# RatDBS-NoBattery.net
KiCad netlist of a schematic drawn in EAGLE
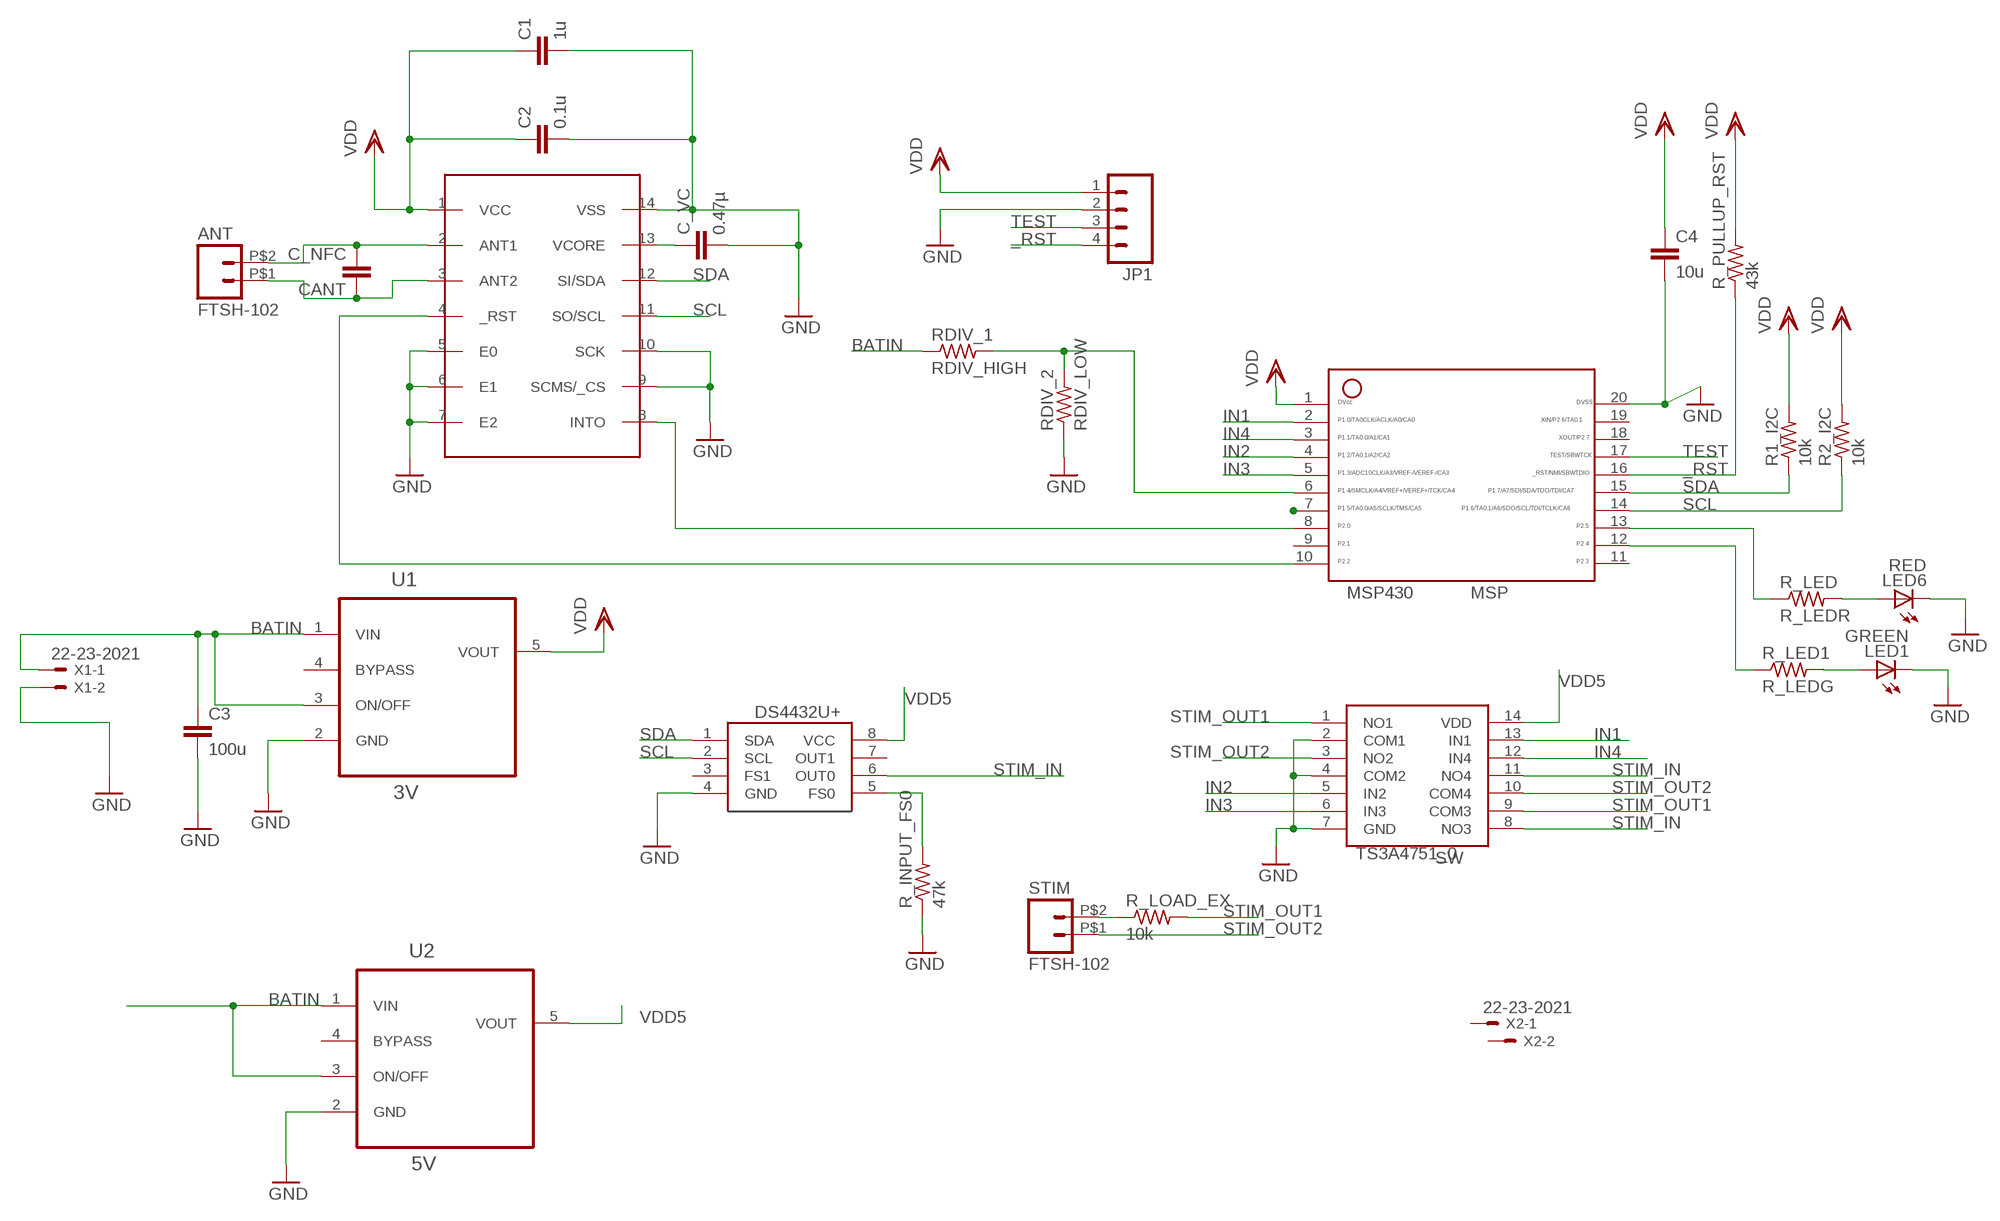
[diagram p0: schematic, sheet 1]

(export (version "E")
  (design (tool "Eeschema 10.0.6"))
  (components
    (comp (ref "ANT")
      (value "FTSH-102")
      (footprint "eagle-import:FTSH-102-DH")
      (libsource (lib "eagle-import") (part "FTSH-102"))
    )
    (comp (ref "C1")
      (value "1u")
      (footprint "eagle-import:C0603")
      (libsource (lib "eagle-import") (part "C-EUC0603"))
    )
    (comp (ref "C2")
      (value "0.1u")
      (footprint "eagle-import:C0603")
      (libsource (lib "eagle-import") (part "C-EUC0603"))
    )
    (comp (ref "C3")
      (value "100u")
      (footprint "eagle-import:C1206")
      (libsource (lib "eagle-import") (part "C-EUC1206"))
    )
    (comp (ref "C4")
      (value "10u")
      (footprint "eagle-import:C1206")
      (libsource (lib "eagle-import") (part "C-EUC1206"))
    )
    (comp (ref "CANT")
      (value "C_NFC")
      (footprint "eagle-import:C0603")
      (libsource (lib "eagle-import") (part "C-EUC0603"))
    )
    (comp (ref "C_VC")
      (value "0.47µ")
      (footprint "eagle-import:C0603")
      (libsource (lib "eagle-import") (part "C-EUC0603"))
    )
    (comp (ref "DS4432U+")
      (value "DS4432U+")
      (footprint "eagle-import:8_PIN")
      (libsource (lib "eagle-import") (part "DS4432U+"))
    )
    (comp (ref "JP1")
      (value "M041.27MM")
      (footprint "eagle-import:1X04-1.27MM")
      (libsource (lib "eagle-import") (part "M041.27MM"))
    )
    (comp (ref "LED1")
      (value "GREEN")
      (footprint "eagle-import:LED-1206")
      (libsource (lib "eagle-import") (part "LED1206"))
    )
    (comp (ref "LED6")
      (value "RED")
      (footprint "eagle-import:LED-1206")
      (libsource (lib "eagle-import") (part "LED1206"))
    )
    (comp (ref "MSP430")
      (value "MSP")
      (footprint "eagle-import:20_PIN")
      (libsource (lib "eagle-import") (part "MSP430"))
    )
    (comp (ref "R1_I2C")
      (value "10k")
      (footprint "eagle-import:R0603")
      (libsource (lib "eagle-import") (part "R-US_R0603"))
    )
    (comp (ref "R2_I2C")
      (value "10k")
      (footprint "eagle-import:R0603")
      (libsource (lib "eagle-import") (part "R-US_R0603"))
    )
    (comp (ref "RDIV_1")
      (value "RDIV_HIGH")
      (footprint "eagle-import:R0603")
      (libsource (lib "eagle-import") (part "R-US_R0603"))
    )
    (comp (ref "RDIV_2")
      (value "RDIV_LOW")
      (footprint "eagle-import:R0603")
      (libsource (lib "eagle-import") (part "R-US_R0603"))
    )
    (comp (ref "R_INPUT_FS0")
      (value "47k")
      (footprint "eagle-import:R0603")
      (libsource (lib "eagle-import") (part "R-US_R0603"))
    )
    (comp (ref "R_LED")
      (value "R_LEDR")
      (footprint "eagle-import:R0603")
      (libsource (lib "eagle-import") (part "R-US_R0603"))
    )
    (comp (ref "R_LED1")
      (value "R_LEDG")
      (footprint "eagle-import:R0603")
      (libsource (lib "eagle-import") (part "R-US_R0603"))
    )
    (comp (ref "R_LOAD_EX")
      (value "10k")
      (footprint "eagle-import:R0603")
      (libsource (lib "eagle-import") (part "R-US_R0603"))
    )
    (comp (ref "R_PULLUP_RST")
      (value "43k")
      (footprint "eagle-import:R0603")
      (libsource (lib "eagle-import") (part "R-US_R0603"))
    )
    (comp (ref "STIM")
      (value "FTSH-102")
      (footprint "eagle-import:FTSH-102-DH")
      (libsource (lib "eagle-import") (part "FTSH-102"))
    )
    (comp (ref "TS3A4751_0")
      (value "SW")
      (footprint "eagle-import:14_PIN")
      (libsource (lib "eagle-import") (part "TS3A4751"))
    )
    (comp (ref "U$1")
      (value "NFC")
      (footprint "eagle-import:PW_R-PDSO-G14")
      (libsource (lib "eagle-import") (part "RF430CL330H"))
    )
    (comp (ref "U1")
      (value "3V")
      (footprint "eagle-import:SOT95P280X145-5N")
      (fields (field (name "MPN") "LP2985A-33DBVTE4"))
      (libsource (lib "eagle-import") (part "LP2985A-33DBVTE4"))
    )
    (comp (ref "U2")
      (value "5V")
      (footprint "eagle-import:SOT95P280X145-5N")
      (fields (field (name "MPN") "LP2985A-33DBVTE4"))
      (libsource (lib "eagle-import") (part "LP2985A-33DBVTE4"))
    )
    (comp (ref "X1")
      (value "22-23-2021")
      (footprint "eagle-import:22-23-2021")
      (fields (field (name "MF") "MOLEX"))
      (libsource (lib "eagle-import") (part "22-23-2021"))
    )
    (comp (ref "X2")
      (value "22-23-2021")
      (footprint "eagle-import:22-23-2021")
      (fields (field (name "MF") "MOLEX"))
      (libsource (lib "eagle-import") (part "22-23-2021"))
    )
  )
  (nets
    (net (code "1") (name "/BATIN") (class "Default")
      (node (ref "C3") (pin "1") (pinfunction "1_1") (pintype "passive"))
      (node (ref "RDIV_1") (pin "1") (pinfunction "1_1") (pintype "passive"))
      (node (ref "U1") (pin "1") (pinfunction "VIN_1") (pintype "power_in"))
      (node (ref "U1") (pin "3") (pinfunction "ON/OFF_3") (pintype "input"))
      (node (ref "U2") (pin "1") (pinfunction "VIN_1") (pintype "power_in"))
      (node (ref "U2") (pin "3") (pinfunction "ON/OFF_3") (pintype "input"))
      (node (ref "X1") (pin "1") (pinfunction "S_1") (pintype "passive"))
    )
    (net (code "2") (name "/IN1") (class "Default")
      (node (ref "MSP430") (pin "2") (pinfunction "2_2") (pintype "bidirectional"))
      (node (ref "TS3A4751_0") (pin "13") (pinfunction "IN1_13") (pintype "bidirectional"))
    )
    (net (code "3") (name "/IN2") (class "Default")
      (node (ref "MSP430") (pin "4") (pinfunction "4_4") (pintype "bidirectional"))
      (node (ref "TS3A4751_0") (pin "5") (pinfunction "IN2_5") (pintype "bidirectional"))
    )
    (net (code "4") (name "/IN3") (class "Default")
      (node (ref "MSP430") (pin "5") (pinfunction "5_5") (pintype "bidirectional"))
      (node (ref "TS3A4751_0") (pin "6") (pinfunction "IN3_6") (pintype "bidirectional"))
    )
    (net (code "5") (name "/IN4") (class "Default")
      (node (ref "MSP430") (pin "3") (pinfunction "3_3") (pintype "bidirectional"))
      (node (ref "TS3A4751_0") (pin "12") (pinfunction "IN4_12") (pintype "bidirectional"))
    )
    (net (code "6") (name "/SCL") (class "Default")
      (node (ref "DS4432U+") (pin "2") (pinfunction "SCL_2") (pintype "bidirectional"))
      (node (ref "MSP430") (pin "14") (pinfunction "14_14") (pintype "bidirectional"))
      (node (ref "R2_I2C") (pin "1") (pinfunction "1_1") (pintype "passive"))
      (node (ref "U$1") (pin "11") (pinfunction "SO/SCL_11") (pintype "bidirectional"))
    )
    (net (code "7") (name "/SDA") (class "Default")
      (node (ref "DS4432U+") (pin "1") (pinfunction "SDA_1") (pintype "bidirectional"))
      (node (ref "MSP430") (pin "15") (pinfunction "15_15") (pintype "bidirectional"))
      (node (ref "R1_I2C") (pin "1") (pinfunction "1_1") (pintype "passive"))
      (node (ref "U$1") (pin "12") (pinfunction "SI/SDA_12") (pintype "bidirectional"))
    )
    (net (code "8") (name "/STIM_IN") (class "Default")
      (node (ref "DS4432U+") (pin "6") (pinfunction "OUT0_6") (pintype "bidirectional"))
      (node (ref "TS3A4751_0") (pin "11") (pinfunction "NO4_11") (pintype "bidirectional"))
      (node (ref "TS3A4751_0") (pin "8") (pinfunction "NO3_8") (pintype "bidirectional"))
    )
    (net (code "9") (name "/STIM_OUT1") (class "Default")
      (node (ref "R_LOAD_EX") (pin "2") (pinfunction "2_2") (pintype "passive"))
      (node (ref "TS3A4751_0") (pin "1") (pinfunction "NO1_1") (pintype "bidirectional"))
      (node (ref "TS3A4751_0") (pin "9") (pinfunction "COM3_9") (pintype "bidirectional"))
    )
    (net (code "10") (name "/STIM_OUT2") (class "Default")
      (node (ref "STIM") (pin "P$1") (pinfunction "1_P$1") (pintype "passive"))
      (node (ref "TS3A4751_0") (pin "10") (pinfunction "COM4_10") (pintype "bidirectional"))
      (node (ref "TS3A4751_0") (pin "3") (pinfunction "NO2_3") (pintype "bidirectional"))
    )
    (net (code "11") (name "/TEST") (class "Default")
      (node (ref "JP1") (pin "3") (pinfunction "3_3") (pintype "passive"))
      (node (ref "MSP430") (pin "17") (pinfunction "17_17") (pintype "bidirectional"))
    )
    (net (code "12") (name "/VDD5") (class "Default")
      (node (ref "DS4432U+") (pin "8") (pinfunction "VCC_8") (pintype "power_in"))
      (node (ref "TS3A4751_0") (pin "14") (pinfunction "VDD_14") (pintype "bidirectional"))
      (node (ref "U2") (pin "5") (pinfunction "VOUT_5") (pintype "output"))
    )
    (net (code "13") (name "/_RST") (class "Default")
      (node (ref "JP1") (pin "4") (pinfunction "4_4") (pintype "passive"))
      (node (ref "MSP430") (pin "16") (pinfunction "16_16") (pintype "bidirectional"))
      (node (ref "R_PULLUP_RST") (pin "1") (pinfunction "1_1") (pintype "passive"))
    )
    (net (code "14") (name "GND") (class "Default")
      (node (ref "C1") (pin "2") (pinfunction "2_2") (pintype "passive"))
      (node (ref "C2") (pin "2") (pinfunction "2_2") (pintype "passive"))
      (node (ref "C3") (pin "2") (pinfunction "2_2") (pintype "passive"))
      (node (ref "C4") (pin "2") (pinfunction "2_2") (pintype "passive"))
      (node (ref "C_VC") (pin "2") (pinfunction "2_2") (pintype "passive"))
      (node (ref "DS4432U+") (pin "4") (pinfunction "GND_4") (pintype "power_in"))
      (node (ref "JP1") (pin "2") (pinfunction "2_2") (pintype "passive"))
      (node (ref "LED1") (pin "C") (pinfunction "C_C") (pintype "passive"))
      (node (ref "LED6") (pin "C") (pinfunction "C_C") (pintype "passive"))
      (node (ref "MSP430") (pin "20") (pinfunction "20_20") (pintype "bidirectional"))
      (node (ref "RDIV_2") (pin "1") (pinfunction "1_1") (pintype "passive"))
      (node (ref "R_INPUT_FS0") (pin "1") (pinfunction "1_1") (pintype "passive"))
      (node (ref "TS3A4751_0") (pin "2") (pinfunction "COM1_2") (pintype "bidirectional"))
      (node (ref "TS3A4751_0") (pin "4") (pinfunction "COM2_4") (pintype "bidirectional"))
      (node (ref "TS3A4751_0") (pin "7") (pinfunction "GND_7") (pintype "bidirectional"))
      (node (ref "U$1") (pin "10") (pinfunction "SCK_10") (pintype "bidirectional"))
      (node (ref "U$1") (pin "14") (pinfunction "VSS_14") (pintype "power_in"))
      (node (ref "U$1") (pin "5") (pinfunction "E0_5") (pintype "bidirectional"))
      (node (ref "U$1") (pin "6") (pinfunction "E1_6") (pintype "bidirectional"))
      (node (ref "U$1") (pin "7") (pinfunction "E2_7") (pintype "bidirectional"))
      (node (ref "U$1") (pin "9") (pinfunction "SCMS/_CS_9") (pintype "bidirectional"))
      (node (ref "U1") (pin "2") (pinfunction "GND_2") (pintype "passive"))
      (node (ref "U2") (pin "2") (pinfunction "GND_2") (pintype "passive"))
      (node (ref "X1") (pin "2") (pinfunction "S_2") (pintype "passive"))
    )
    (net (code "15") (name "Net-(ANT-1)") (class "Default")
      (node (ref "ANT") (pin "P$1") (pinfunction "1_P$1") (pintype "passive"))
      (node (ref "CANT") (pin "1") (pinfunction "1_1") (pintype "passive"))
      (node (ref "U$1") (pin "3") (pinfunction "ANT2_3") (pintype "bidirectional"))
    )
    (net (code "16") (name "Net-(ANT-2)") (class "Default")
      (node (ref "ANT") (pin "P$2") (pinfunction "2_P$2") (pintype "passive"))
      (node (ref "CANT") (pin "2") (pinfunction "2_2") (pintype "passive"))
      (node (ref "U$1") (pin "2") (pinfunction "ANT1_2") (pintype "bidirectional"))
    )
    (net (code "17") (name "Net-(DS4432U+-FS0)") (class "Default")
      (node (ref "DS4432U+") (pin "5") (pinfunction "FS0_5") (pintype "bidirectional"))
      (node (ref "R_INPUT_FS0") (pin "2") (pinfunction "2_2") (pintype "passive"))
    )
    (net (code "18") (name "Net-(LED1-PadA)") (class "Default")
      (node (ref "LED1") (pin "A") (pinfunction "A_A") (pintype "passive"))
      (node (ref "R_LED1") (pin "2") (pinfunction "2_2") (pintype "passive"))
    )
    (net (code "19") (name "Net-(LED6-PadA)") (class "Default")
      (node (ref "LED6") (pin "A") (pinfunction "A_A") (pintype "passive"))
      (node (ref "R_LED") (pin "2") (pinfunction "2_2") (pintype "passive"))
    )
    (net (code "20") (name "Net-(MSP430-Pad6)") (class "Default")
      (node (ref "MSP430") (pin "6") (pinfunction "6_6") (pintype "bidirectional"))
      (node (ref "RDIV_1") (pin "2") (pinfunction "2_2") (pintype "passive"))
      (node (ref "RDIV_2") (pin "2") (pinfunction "2_2") (pintype "passive"))
    )
    (net (code "21") (name "Net-(MSP430-Pad12)") (class "Default")
      (node (ref "MSP430") (pin "12") (pinfunction "12_12") (pintype "bidirectional"))
      (node (ref "R_LED1") (pin "1") (pinfunction "1_1") (pintype "passive"))
    )
    (net (code "22") (name "Net-(MSP430-Pad13)") (class "Default")
      (node (ref "MSP430") (pin "13") (pinfunction "13_13") (pintype "bidirectional"))
      (node (ref "R_LED") (pin "1") (pinfunction "1_1") (pintype "passive"))
    )
    (net (code "23") (name "Net-(STIM-2)") (class "Default")
      (node (ref "R_LOAD_EX") (pin "1") (pinfunction "1_1") (pintype "passive"))
      (node (ref "STIM") (pin "P$2") (pinfunction "2_P$2") (pintype "passive"))
    )
    (net (code "24") (name "Net-(U$1-INTO)") (class "Default")
      (node (ref "MSP430") (pin "8") (pinfunction "8_8") (pintype "bidirectional"))
      (node (ref "U$1") (pin "8") (pinfunction "INTO_8") (pintype "bidirectional"))
    )
    (net (code "25") (name "Net-(U$1-VCORE)") (class "Default")
      (node (ref "C_VC") (pin "1") (pinfunction "1_1") (pintype "passive"))
      (node (ref "U$1") (pin "13") (pinfunction "VCORE_13") (pintype "bidirectional"))
    )
    (net (code "26") (name "Net-(U$1-_RST)") (class "Default")
      (node (ref "MSP430") (pin "10") (pinfunction "10_10") (pintype "bidirectional"))
      (node (ref "U$1") (pin "4") (pinfunction "_RST_4") (pintype "bidirectional"))
    )
    (net (code "27") (name "VDD") (class "Default")
      (node (ref "C1") (pin "1") (pinfunction "1_1") (pintype "passive"))
      (node (ref "C2") (pin "1") (pinfunction "1_1") (pintype "passive"))
      (node (ref "C4") (pin "1") (pinfunction "1_1") (pintype "passive"))
      (node (ref "JP1") (pin "1") (pinfunction "1_1") (pintype "passive"))
      (node (ref "MSP430") (pin "1") (pinfunction "1_1") (pintype "bidirectional"))
      (node (ref "R1_I2C") (pin "2") (pinfunction "2_2") (pintype "passive"))
      (node (ref "R2_I2C") (pin "2") (pinfunction "2_2") (pintype "passive"))
      (node (ref "R_PULLUP_RST") (pin "2") (pinfunction "2_2") (pintype "passive"))
      (node (ref "U$1") (pin "1") (pinfunction "VCC_1") (pintype "power_in"))
      (node (ref "U1") (pin "5") (pinfunction "VOUT_5") (pintype "output"))
    )
    (net (code "28") (name "unconnected-(DS4432U+-FS1-Pad3)") (class "Default")
      (node (ref "DS4432U+") (pin "3") (pinfunction "FS1_3") (pintype "bidirectional"))
    )
    (net (code "29") (name "unconnected-(DS4432U+-OUT1-Pad7)") (class "Default")
      (node (ref "DS4432U+") (pin "7") (pinfunction "OUT1_7") (pintype "bidirectional"))
    )
    (net (code "30") (name "unconnected-(MSP430-Pad7)") (class "Default")
      (node (ref "MSP430") (pin "7") (pinfunction "7_7") (pintype "bidirectional"))
    )
    (net (code "31") (name "unconnected-(MSP430-Pad9)") (class "Default")
      (node (ref "MSP430") (pin "9") (pinfunction "9_9") (pintype "bidirectional"))
    )
    (net (code "32") (name "unconnected-(MSP430-Pad11)") (class "Default")
      (node (ref "MSP430") (pin "11") (pinfunction "11_11") (pintype "bidirectional"))
    )
    (net (code "33") (name "unconnected-(MSP430-Pad18)") (class "Default")
      (node (ref "MSP430") (pin "18") (pinfunction "18_18") (pintype "bidirectional"))
    )
    (net (code "34") (name "unconnected-(MSP430-Pad19)") (class "Default")
      (node (ref "MSP430") (pin "19") (pinfunction "19_19") (pintype "bidirectional"))
    )
    (net (code "35") (name "unconnected-(U1-BYPASS-Pad4)") (class "Default")
      (node (ref "U1") (pin "4") (pinfunction "BYPASS_4") (pintype "input"))
    )
    (net (code "36") (name "unconnected-(U2-BYPASS-Pad4)") (class "Default")
      (node (ref "U2") (pin "4") (pinfunction "BYPASS_4") (pintype "input"))
    )
    (net (code "37") (name "unconnected-(X2A-S-Pad1)") (class "Default")
      (node (ref "X2") (pin "1") (pinfunction "S_1") (pintype "passive"))
    )
    (net (code "38") (name "unconnected-(X2B-S-Pad2)") (class "Default")
      (node (ref "X2") (pin "2") (pinfunction "S_2") (pintype "passive"))
    )
  )
)
